# design.net
KiCad netlist of a schematic drawn in Altium Designer
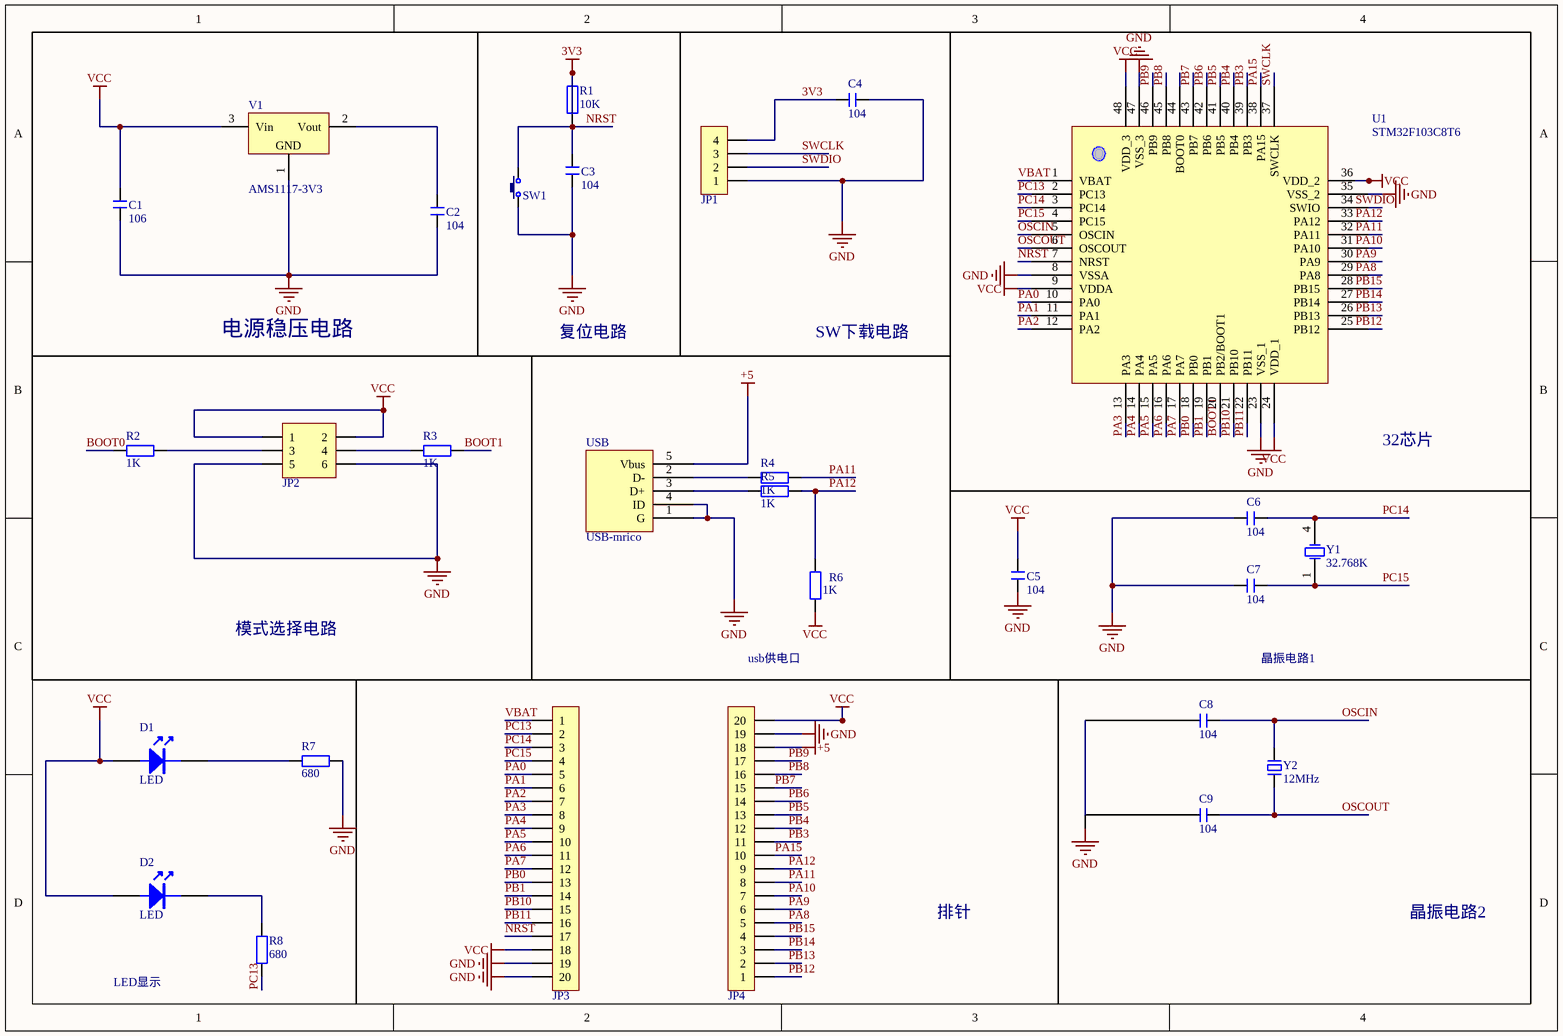
[diagram p0: 最小系统.SchDoc]

(export (version "E")
  (design (tool "Eeschema 10.0.6"))
  (components
    (comp (ref "C1")
      (value "106")
      (footprint "C 0201_L")
      (description "贴片电容")
      (libsource (lib "0.1 - 电阻-电容-电感") (part "C"))
    )
    (comp (ref "C2")
      (value "104")
      (footprint "C 0201_L")
      (description "贴片电容")
      (libsource (lib "0.1 - 电阻-电容-电感") (part "C"))
    )
    (comp (ref "C3")
      (value "104")
      (footprint "C 0201_L")
      (description "贴片电容")
      (libsource (lib "0.1 - 电阻-电容-电感") (part "C"))
    )
    (comp (ref "C4")
      (value "104")
      (footprint "C 0201_L")
      (description "贴片电容")
      (libsource (lib "0.1 - 电阻-电容-电感") (part "C"))
    )
    (comp (ref "C5")
      (value "104")
      (footprint "C 0201_L")
      (description "贴片电容")
      (libsource (lib "0.1 - 电阻-电容-电感") (part "C"))
    )
    (comp (ref "C6")
      (value "104")
      (footprint "C 0201_L")
      (description "贴片电容")
      (libsource (lib "0.1 - 电阻-电容-电感") (part "C"))
    )
    (comp (ref "C7")
      (value "104")
      (footprint "C 0201_L")
      (description "贴片电容")
      (libsource (lib "0.1 - 电阻-电容-电感") (part "C"))
    )
    (comp (ref "C8")
      (value "104")
      (footprint "C 0201_L")
      (description "贴片电容")
      (libsource (lib "0.1 - 电阻-电容-电感") (part "C"))
    )
    (comp (ref "C9")
      (value "104")
      (footprint "C 0201_L")
      (description "贴片电容")
      (libsource (lib "0.1 - 电阻-电容-电感") (part "C"))
    )
    (comp (ref "D1") (value "LED") (footprint "LED 0805G") (libsource (lib "stm32原理图库") (part "LED")))
    (comp (ref "D2") (value "LED") (footprint "LED 0805G") (libsource (lib "stm32原理图库") (part "LED")))
    (comp (ref "JP1")
      (value "HDR-1X4")
      (footprint "XH2.54-WI-4P")
      (description "4P接插件")
      (fields (field (name "版权归属") "封装库来自淘宝 ID：黄晶宝石"))
      (libsource (lib "5.3 - 接插件-脚距2.54 (100mil) ") (part "Header 4"))
    )
    (comp (ref "JP2")
      (value "Header3X2")
      (footprint "IDC2.54-LI-2x3P")
      (description "3*2P接插件")
      (fields (field (name "版权归属") "封装库来自淘宝 ID：黄晶宝石"))
      (libsource (lib "5.3 - 接插件-脚距2.54 (100mil) ") (part "Header 3X2"))
    )
    (comp (ref "JP3")
      (value "HDR-1X20")
      (footprint "HDR2.54-LI-20P")
      (description "20P接插件")
      (fields (field (name "版权归属") "封装库来自淘宝 ID：黄晶宝石"))
      (libsource (lib "5.3 - 接插件-脚距2.54 (100mil) ") (part "Header 20"))
    )
    (comp (ref "JP4")
      (value "HDR-1X20")
      (footprint "HDR2.54-LI-20P")
      (description "20P接插件")
      (fields (field (name "版权归属") "封装库来自淘宝 ID：黄晶宝石"))
      (libsource (lib "") (part "Header 20_1"))
    )
    (comp (ref "R1")
      (value "10K")
      (footprint "R 0201_L")
      (description "贴片电阻")
      (fields (field (name "版权归属") "来自淘宝 ID：黄晶宝石"))
      (libsource (lib "0.1 - 电阻-电容-电感") (part "R"))
    )
    (comp (ref "R2")
      (value "1K")
      (footprint "R 0201_L")
      (description "贴片电阻")
      (fields (field (name "版权归属") "来自淘宝 ID：黄晶宝石"))
      (libsource (lib "0.1 - 电阻-电容-电感") (part "R"))
    )
    (comp (ref "R3")
      (value "1K")
      (footprint "R 0201_L")
      (description "贴片电阻")
      (fields (field (name "版权归属") "来自淘宝 ID：黄晶宝石"))
      (libsource (lib "0.1 - 电阻-电容-电感") (part "R"))
    )
    (comp (ref "R4")
      (value "1K")
      (footprint "R 0201_L")
      (description "贴片电阻")
      (fields (field (name "版权归属") "来自淘宝 ID：黄晶宝石"))
      (libsource (lib "0.1 - 电阻-电容-电感") (part "R"))
    )
    (comp (ref "R5")
      (value "1K")
      (footprint "R 0201_L")
      (description "贴片电阻")
      (fields (field (name "版权归属") "来自淘宝 ID：黄晶宝石"))
      (libsource (lib "0.1 - 电阻-电容-电感") (part "R"))
    )
    (comp (ref "R6")
      (value "1K")
      (footprint "R 0201_L")
      (description "贴片电阻")
      (fields (field (name "版权归属") "来自淘宝 ID：黄晶宝石"))
      (libsource (lib "0.1 - 电阻-电容-电感") (part "R"))
    )
    (comp (ref "R7")
      (value "680")
      (footprint "R 0201_L")
      (description "贴片电阻")
      (fields (field (name "版权归属") "来自淘宝 ID：黄晶宝石"))
      (libsource (lib "0.1 - 电阻-电容-电感") (part "R"))
    )
    (comp (ref "R8")
      (value "680")
      (footprint "R 0201_L")
      (description "贴片电阻")
      (fields (field (name "版权归属") "来自淘宝 ID：黄晶宝石"))
      (libsource (lib "0.1 - 电阻-电容-电感") (part "R"))
    )
    (comp (ref "SW1")
      (value "3x6x5")
      (footprint "TSW SMD-3*6*2.5")
      (description "3x6轻触开关")
      (fields (field (name "版权归属") "封装库来自淘宝 ID：黄晶宝石"))
      (libsource (lib "0.7 - 常用按键-开关") (part "TSW 3x6"))
    )
    (comp (ref "U1")
      (value "STM32F103C8T6")
      (footprint "TQFP48 7x7_L")
      (libsource (lib "stm32原理图库") (part "STM32F103C8T6"))
    )
    (comp (ref "USB")
      (value "USB-mrico")
      (footprint "USB-micro_B")
      (libsource (lib "stm32原理图库") (part "usb-STM"))
    )
    (comp (ref "V1")
      (value "AMS1117-3V3")
      (footprint "SOT223_L")
      (description "三端稳压芯片")
      (libsource (lib "1.1 - 电源类芯片") (part "AMS1117"))
    )
    (comp (ref "Y1")
      (value "32.768K")
      (footprint "MC-306")
      (fields (field (name "PUBLISHER") "Altium Limited"))
      (libsource (lib "stm32原理图库") (part "XTAL"))
    )
    (comp (ref "Y2")
      (value "12MHz")
      (footprint "OSC HC-49S")
      (description "2脚无源脚晶振")
      (fields (field (name "版权归属") "封装库来自淘宝卖家 ID：黄晶宝石"))
      (libsource (lib "2.0 - 保险丝-晶振-光耦") (part "XTAL-2P"))
    )
  )
  (nets
    (net (code "1") (name "+5") (class "Default")
      (node (ref "JP4") (pin "18") (pinfunction "18_18") (pintype "passive"))
      (node (ref "USB") (pin "5") (pinfunction "Vbus_5") (pintype "passive"))
    )
    (net (code "3") (name "/BOOT0") (class "Default")
      (node (ref "R2") (pin "1") (pinfunction "1_1") (pintype "passive"))
    )
    (net (code "4") (name "/BOOT1") (class "Default")
      (node (ref "R3") (pin "2") (pinfunction "2_2") (pintype "passive"))
      (node (ref "U1") (pin "20") (pinfunction "PB2/BOOT1_20") (pintype "passive"))
    )
    (net (code "5") (name "/NRST") (class "Default")
      (node (ref "C3") (pin "2") (pinfunction "2_2") (pintype "passive"))
      (node (ref "JP3") (pin "17") (pinfunction "17_17") (pintype "passive"))
      (node (ref "R1") (pin "1") (pinfunction "1_1") (pintype "passive"))
      (node (ref "SW1") (pin "2") (pinfunction "2_2") (pintype "passive"))
      (node (ref "U1") (pin "7") (pinfunction "NRST_7") (pintype "passive"))
    )
    (net (code "6") (name "/OSCIN") (class "Default")
      (node (ref "C8") (pin "2") (pinfunction "2_2") (pintype "passive"))
      (node (ref "U1") (pin "5") (pinfunction "OSCIN_5") (pintype "passive"))
      (node (ref "Y2") (pin "2") (pinfunction "2_2") (pintype "passive"))
    )
    (net (code "7") (name "/OSCOUT") (class "Default")
      (node (ref "C9") (pin "2") (pinfunction "2_2") (pintype "passive"))
      (node (ref "U1") (pin "6") (pinfunction "OSCOUT_6") (pintype "passive"))
      (node (ref "Y2") (pin "1") (pinfunction "1_1") (pintype "passive"))
    )
    (net (code "8") (name "/PA0") (class "Default")
      (node (ref "JP3") (pin "5") (pinfunction "5_5") (pintype "passive"))
      (node (ref "U1") (pin "10") (pinfunction "PA0_10") (pintype "passive"))
    )
    (net (code "9") (name "/PA1") (class "Default")
      (node (ref "JP3") (pin "6") (pinfunction "6_6") (pintype "passive"))
      (node (ref "U1") (pin "11") (pinfunction "PA1_11") (pintype "passive"))
    )
    (net (code "10") (name "/PA2") (class "Default")
      (node (ref "JP3") (pin "7") (pinfunction "7_7") (pintype "passive"))
      (node (ref "U1") (pin "12") (pinfunction "PA2_12") (pintype "passive"))
    )
    (net (code "11") (name "/PA3") (class "Default")
      (node (ref "JP3") (pin "8") (pinfunction "8_8") (pintype "passive"))
      (node (ref "U1") (pin "13") (pinfunction "PA3_13") (pintype "passive"))
    )
    (net (code "12") (name "/PA4") (class "Default")
      (node (ref "JP3") (pin "9") (pinfunction "9_9") (pintype "passive"))
      (node (ref "U1") (pin "14") (pinfunction "PA4_14") (pintype "passive"))
    )
    (net (code "13") (name "/PA5") (class "Default")
      (node (ref "JP3") (pin "10") (pinfunction "10_10") (pintype "passive"))
      (node (ref "U1") (pin "15") (pinfunction "PA5_15") (pintype "passive"))
    )
    (net (code "14") (name "/PA6") (class "Default")
      (node (ref "JP3") (pin "11") (pinfunction "11_11") (pintype "passive"))
      (node (ref "U1") (pin "16") (pinfunction "PA6_16") (pintype "passive"))
    )
    (net (code "15") (name "/PA7") (class "Default")
      (node (ref "JP3") (pin "12") (pinfunction "12_12") (pintype "passive"))
      (node (ref "U1") (pin "17") (pinfunction "PA7_17") (pintype "passive"))
    )
    (net (code "16") (name "/PA8") (class "Default")
      (node (ref "JP4") (pin "5") (pinfunction "5_5") (pintype "passive"))
    )
    (net (code "17") (name "/PA9") (class "Default")
      (node (ref "JP4") (pin "6") (pinfunction "6_6") (pintype "passive"))
    )
    (net (code "18") (name "/PA10") (class "Default")
      (node (ref "JP4") (pin "7") (pinfunction "7_7") (pintype "passive"))
    )
    (net (code "19") (name "/PA11") (class "Default")
      (node (ref "JP4") (pin "8") (pinfunction "8_8") (pintype "passive"))
      (node (ref "R4") (pin "2") (pinfunction "2_2") (pintype "passive"))
    )
    (net (code "20") (name "/PA12") (class "Default")
      (node (ref "JP4") (pin "9") (pinfunction "9_9") (pintype "passive"))
      (node (ref "R5") (pin "2") (pinfunction "2_2") (pintype "passive"))
      (node (ref "R6") (pin "2") (pinfunction "2_2") (pintype "passive"))
    )
    (net (code "21") (name "/PA15") (class "Default")
      (node (ref "JP4") (pin "10") (pinfunction "10_10") (pintype "passive"))
      (node (ref "U1") (pin "38") (pinfunction "PA15_38") (pintype "passive"))
    )
    (net (code "22") (name "/PB0") (class "Default")
      (node (ref "JP3") (pin "13") (pinfunction "13_13") (pintype "passive"))
      (node (ref "U1") (pin "18") (pinfunction "PB0_18") (pintype "passive"))
    )
    (net (code "23") (name "/PB1") (class "Default")
      (node (ref "JP3") (pin "14") (pinfunction "14_14") (pintype "passive"))
      (node (ref "U1") (pin "19") (pinfunction "PB1_19") (pintype "passive"))
    )
    (net (code "24") (name "/PB3") (class "Default")
      (node (ref "JP4") (pin "11") (pinfunction "11_11") (pintype "passive"))
      (node (ref "U1") (pin "39") (pinfunction "PB3_39") (pintype "passive"))
    )
    (net (code "25") (name "/PB4") (class "Default")
      (node (ref "JP4") (pin "12") (pinfunction "12_12") (pintype "passive"))
      (node (ref "U1") (pin "40") (pinfunction "PB4_40") (pintype "passive"))
    )
    (net (code "26") (name "/PB5") (class "Default")
      (node (ref "JP4") (pin "13") (pinfunction "13_13") (pintype "passive"))
      (node (ref "U1") (pin "41") (pinfunction "PB5_41") (pintype "passive"))
    )
    (net (code "27") (name "/PB6") (class "Default")
      (node (ref "JP4") (pin "14") (pinfunction "14_14") (pintype "passive"))
      (node (ref "U1") (pin "42") (pinfunction "PB6_42") (pintype "passive"))
    )
    (net (code "28") (name "/PB7") (class "Default")
      (node (ref "JP4") (pin "15") (pinfunction "15_15") (pintype "passive"))
      (node (ref "U1") (pin "43") (pinfunction "PB7_43") (pintype "passive"))
    )
    (net (code "29") (name "/PB8") (class "Default")
      (node (ref "JP4") (pin "16") (pinfunction "16_16") (pintype "passive"))
      (node (ref "U1") (pin "45") (pinfunction "PB8_45") (pintype "passive"))
    )
    (net (code "30") (name "/PB9") (class "Default")
      (node (ref "JP4") (pin "17") (pinfunction "17_17") (pintype "passive"))
      (node (ref "U1") (pin "46") (pinfunction "PB9_46") (pintype "passive"))
    )
    (net (code "31") (name "/PB10") (class "Default")
      (node (ref "JP3") (pin "15") (pinfunction "15_15") (pintype "passive"))
      (node (ref "U1") (pin "21") (pinfunction "PB10_21") (pintype "passive"))
    )
    (net (code "32") (name "/PB11") (class "Default")
      (node (ref "JP3") (pin "16") (pinfunction "16_16") (pintype "passive"))
      (node (ref "U1") (pin "22") (pinfunction "PB11_22") (pintype "passive"))
    )
    (net (code "33") (name "/PB12") (class "Default")
      (node (ref "JP4") (pin "1") (pinfunction "1_1") (pintype "passive"))
    )
    (net (code "34") (name "/PB13") (class "Default")
      (node (ref "JP4") (pin "2") (pinfunction "2_2") (pintype "passive"))
    )
    (net (code "35") (name "/PB14") (class "Default")
      (node (ref "JP4") (pin "3") (pinfunction "3_3") (pintype "passive"))
    )
    (net (code "36") (name "/PB15") (class "Default")
      (node (ref "JP4") (pin "4") (pinfunction "4_4") (pintype "passive"))
    )
    (net (code "37") (name "/PC13") (class "Default")
      (node (ref "JP3") (pin "2") (pinfunction "2_2") (pintype "passive"))
      (node (ref "R8") (pin "2") (pinfunction "2_2") (pintype "passive"))
      (node (ref "U1") (pin "2") (pinfunction "PC13_2") (pintype "passive"))
    )
    (net (code "38") (name "/PC14") (class "Default")
      (node (ref "C6") (pin "1") (pinfunction "1_1") (pintype "passive"))
      (node (ref "JP3") (pin "3") (pinfunction "3_3") (pintype "passive"))
      (node (ref "U1") (pin "3") (pinfunction "PC14_3") (pintype "passive"))
      (node (ref "Y1") (pin "4") (pinfunction "OSC2_4") (pintype "passive"))
    )
    (net (code "39") (name "/PC15") (class "Default")
      (node (ref "C7") (pin "1") (pinfunction "1_1") (pintype "passive"))
      (node (ref "JP3") (pin "4") (pinfunction "4_4") (pintype "passive"))
      (node (ref "U1") (pin "4") (pinfunction "PC15_4") (pintype "passive"))
      (node (ref "Y1") (pin "1") (pinfunction "OSC1_1") (pintype "passive"))
    )
    (net (code "40") (name "/SWCLK") (class "Default")
      (node (ref "JP1") (pin "3") (pinfunction "3_3") (pintype "passive"))
      (node (ref "U1") (pin "37") (pinfunction "SWCLK_37") (pintype "passive"))
    )
    (net (code "41") (name "/SWDIO") (class "Default")
      (node (ref "JP1") (pin "2") (pinfunction "2_2") (pintype "passive"))
    )
    (net (code "42") (name "/VBAT") (class "Default")
      (node (ref "JP3") (pin "1") (pinfunction "1_1") (pintype "passive"))
      (node (ref "U1") (pin "1") (pinfunction "VBAT_1") (pintype "passive"))
    )
    (net (code "43") (name "3V3") (class "Default")
      (node (ref "C4") (pin "2") (pinfunction "2_2") (pintype "passive"))
      (node (ref "JP1") (pin "4") (pinfunction "4_4") (pintype "passive"))
      (node (ref "R1") (pin "2") (pinfunction "2_2") (pintype "passive"))
    )
    (net (code "44") (name "GND") (class "Default")
      (node (ref "C1") (pin "1") (pinfunction "1_1") (pintype "passive"))
      (node (ref "C2") (pin "1") (pinfunction "1_1") (pintype "passive"))
      (node (ref "C3") (pin "1") (pinfunction "1_1") (pintype "passive"))
      (node (ref "C4") (pin "1") (pinfunction "1_1") (pintype "passive"))
      (node (ref "C5") (pin "1") (pinfunction "1_1") (pintype "passive"))
      (node (ref "C6") (pin "2") (pinfunction "2_2") (pintype "passive"))
      (node (ref "C7") (pin "2") (pinfunction "2_2") (pintype "passive"))
      (node (ref "JP1") (pin "1") (pinfunction "1_1") (pintype "passive"))
      (node (ref "JP2") (pin "5") (pinfunction "5_5") (pintype "passive"))
      (node (ref "JP2") (pin "6") (pinfunction "6_6") (pintype "passive"))
      (node (ref "JP3") (pin "19") (pinfunction "19_19") (pintype "passive"))
      (node (ref "JP3") (pin "20") (pinfunction "20_20") (pintype "passive"))
      (node (ref "JP4") (pin "19") (pinfunction "19_19") (pintype "passive"))
      (node (ref "R7") (pin "1") (pinfunction "1_1") (pintype "passive"))
      (node (ref "SW1") (pin "1") (pinfunction "1_1") (pintype "passive"))
      (node (ref "U1") (pin "23") (pinfunction "VSS_1_23") (pintype "passive"))
      (node (ref "U1") (pin "35") (pinfunction "VSS_2_35") (pintype "passive"))
      (node (ref "U1") (pin "47") (pinfunction "VSS_3_47") (pintype "passive"))
      (node (ref "U1") (pin "8") (pinfunction "VSSA_8") (pintype "passive"))
      (node (ref "USB") (pin "1") (pinfunction "G_1") (pintype "passive"))
      (node (ref "USB") (pin "4") (pinfunction "ID_4") (pintype "passive"))
      (node (ref "V1") (pin "1") (pinfunction "GND_1") (pintype "passive"))
    )
    (net (code "45") (name "Net-(D1-Pad2)") (class "Default")
      (node (ref "D1") (pin "2") (pinfunction "2_2") (pintype "passive"))
      (node (ref "R7") (pin "2") (pinfunction "2_2") (pintype "passive"))
    )
    (net (code "46") (name "Net-(D2-Pad2)") (class "Default")
      (node (ref "D2") (pin "2") (pinfunction "2_2") (pintype "passive"))
      (node (ref "R8") (pin "1") (pinfunction "1_1") (pintype "passive"))
    )
    (net (code "47") (name "Net-(JP2-Pad3)") (class "Default")
      (node (ref "JP2") (pin "3") (pinfunction "3_3") (pintype "passive"))
      (node (ref "R2") (pin "2") (pinfunction "2_2") (pintype "passive"))
    )
    (net (code "48") (name "Net-(JP2-Pad4)") (class "Default")
      (node (ref "JP2") (pin "4") (pinfunction "4_4") (pintype "passive"))
      (node (ref "R3") (pin "1") (pinfunction "1_1") (pintype "passive"))
    )
    (net (code "49") (name "Net-(USB-D+)") (class "Default")
      (node (ref "R5") (pin "1") (pinfunction "1_1") (pintype "passive"))
      (node (ref "USB") (pin "3") (pinfunction "D+_3") (pintype "passive"))
    )
    (net (code "50") (name "Net-(USB-D-)") (class "Default")
      (node (ref "R4") (pin "1") (pinfunction "1_1") (pintype "passive"))
      (node (ref "USB") (pin "2") (pinfunction "D-_2") (pintype "passive"))
    )
    (net (code "51") (name "Net-(V1-Vout)") (class "Default")
      (node (ref "C2") (pin "2") (pinfunction "2_2") (pintype "passive"))
      (node (ref "V1") (pin "2") (pinfunction "Vout_2") (pintype "passive"))
    )
    (net (code "52") (name "VCC") (class "Default")
      (node (ref "C1") (pin "2") (pinfunction "2_2") (pintype "passive"))
      (node (ref "C5") (pin "2") (pinfunction "2_2") (pintype "passive"))
      (node (ref "D1") (pin "1") (pinfunction "1_1") (pintype "passive"))
      (node (ref "D2") (pin "1") (pinfunction "1_1") (pintype "passive"))
      (node (ref "JP2") (pin "1") (pinfunction "1_1") (pintype "passive"))
      (node (ref "JP2") (pin "2") (pinfunction "2_2") (pintype "passive"))
      (node (ref "JP3") (pin "18") (pinfunction "18_18") (pintype "passive"))
      (node (ref "JP4") (pin "20") (pinfunction "20_20") (pintype "passive"))
      (node (ref "R6") (pin "1") (pinfunction "1_1") (pintype "passive"))
      (node (ref "U1") (pin "24") (pinfunction "VDD_1_24") (pintype "passive"))
      (node (ref "U1") (pin "36") (pinfunction "VDD_2_36") (pintype "passive"))
      (node (ref "U1") (pin "48") (pinfunction "VDD_3_48") (pintype "passive"))
      (node (ref "U1") (pin "9") (pinfunction "VDDA_9") (pintype "passive"))
      (node (ref "V1") (pin "3") (pinfunction "Vin_3") (pintype "passive"))
    )
    (net (code "53") (name "unconnected-(C8-Pad1)") (class "Default")
      (node (ref "C8") (pin "1") (pinfunction "1_1") (pintype "passive"))
    )
    (net (code "54") (name "unconnected-(C9-Pad1)") (class "Default")
      (node (ref "C9") (pin "1") (pinfunction "1_1") (pintype "passive"))
    )
    (net (code "55") (name "unconnected-(U1-BOOT0-Pad44)") (class "Default")
      (node (ref "U1") (pin "44") (pinfunction "BOOT0_44") (pintype "passive"))
    )
    (net (code "56") (name "unconnected-(U1-PA8-Pad29)") (class "Default")
      (node (ref "U1") (pin "29") (pinfunction "PA8_29") (pintype "passive"))
    )
    (net (code "57") (name "unconnected-(U1-PA9-Pad30)") (class "Default")
      (node (ref "U1") (pin "30") (pinfunction "PA9_30") (pintype "passive"))
    )
    (net (code "58") (name "unconnected-(U1-PA10-Pad31)") (class "Default")
      (node (ref "U1") (pin "31") (pinfunction "PA10_31") (pintype "passive"))
    )
    (net (code "59") (name "unconnected-(U1-PA11-Pad32)") (class "Default")
      (node (ref "U1") (pin "32") (pinfunction "PA11_32") (pintype "passive"))
    )
    (net (code "60") (name "unconnected-(U1-PA12-Pad33)") (class "Default")
      (node (ref "U1") (pin "33") (pinfunction "PA12_33") (pintype "passive"))
    )
    (net (code "61") (name "unconnected-(U1-PB12-Pad25)") (class "Default")
      (node (ref "U1") (pin "25") (pinfunction "PB12_25") (pintype "passive"))
    )
    (net (code "62") (name "unconnected-(U1-PB13-Pad26)") (class "Default")
      (node (ref "U1") (pin "26") (pinfunction "PB13_26") (pintype "passive"))
    )
    (net (code "63") (name "unconnected-(U1-PB14-Pad27)") (class "Default")
      (node (ref "U1") (pin "27") (pinfunction "PB14_27") (pintype "passive"))
    )
    (net (code "64") (name "unconnected-(U1-PB15-Pad28)") (class "Default")
      (node (ref "U1") (pin "28") (pinfunction "PB15_28") (pintype "passive"))
    )
    (net (code "65") (name "unconnected-(U1-SWIO-Pad34)") (class "Default")
      (node (ref "U1") (pin "34") (pinfunction "SWIO_34") (pintype "passive"))
    )
  )
)
